# VBT6.net
KiCad netlist of a schematic drawn in Altium Designer
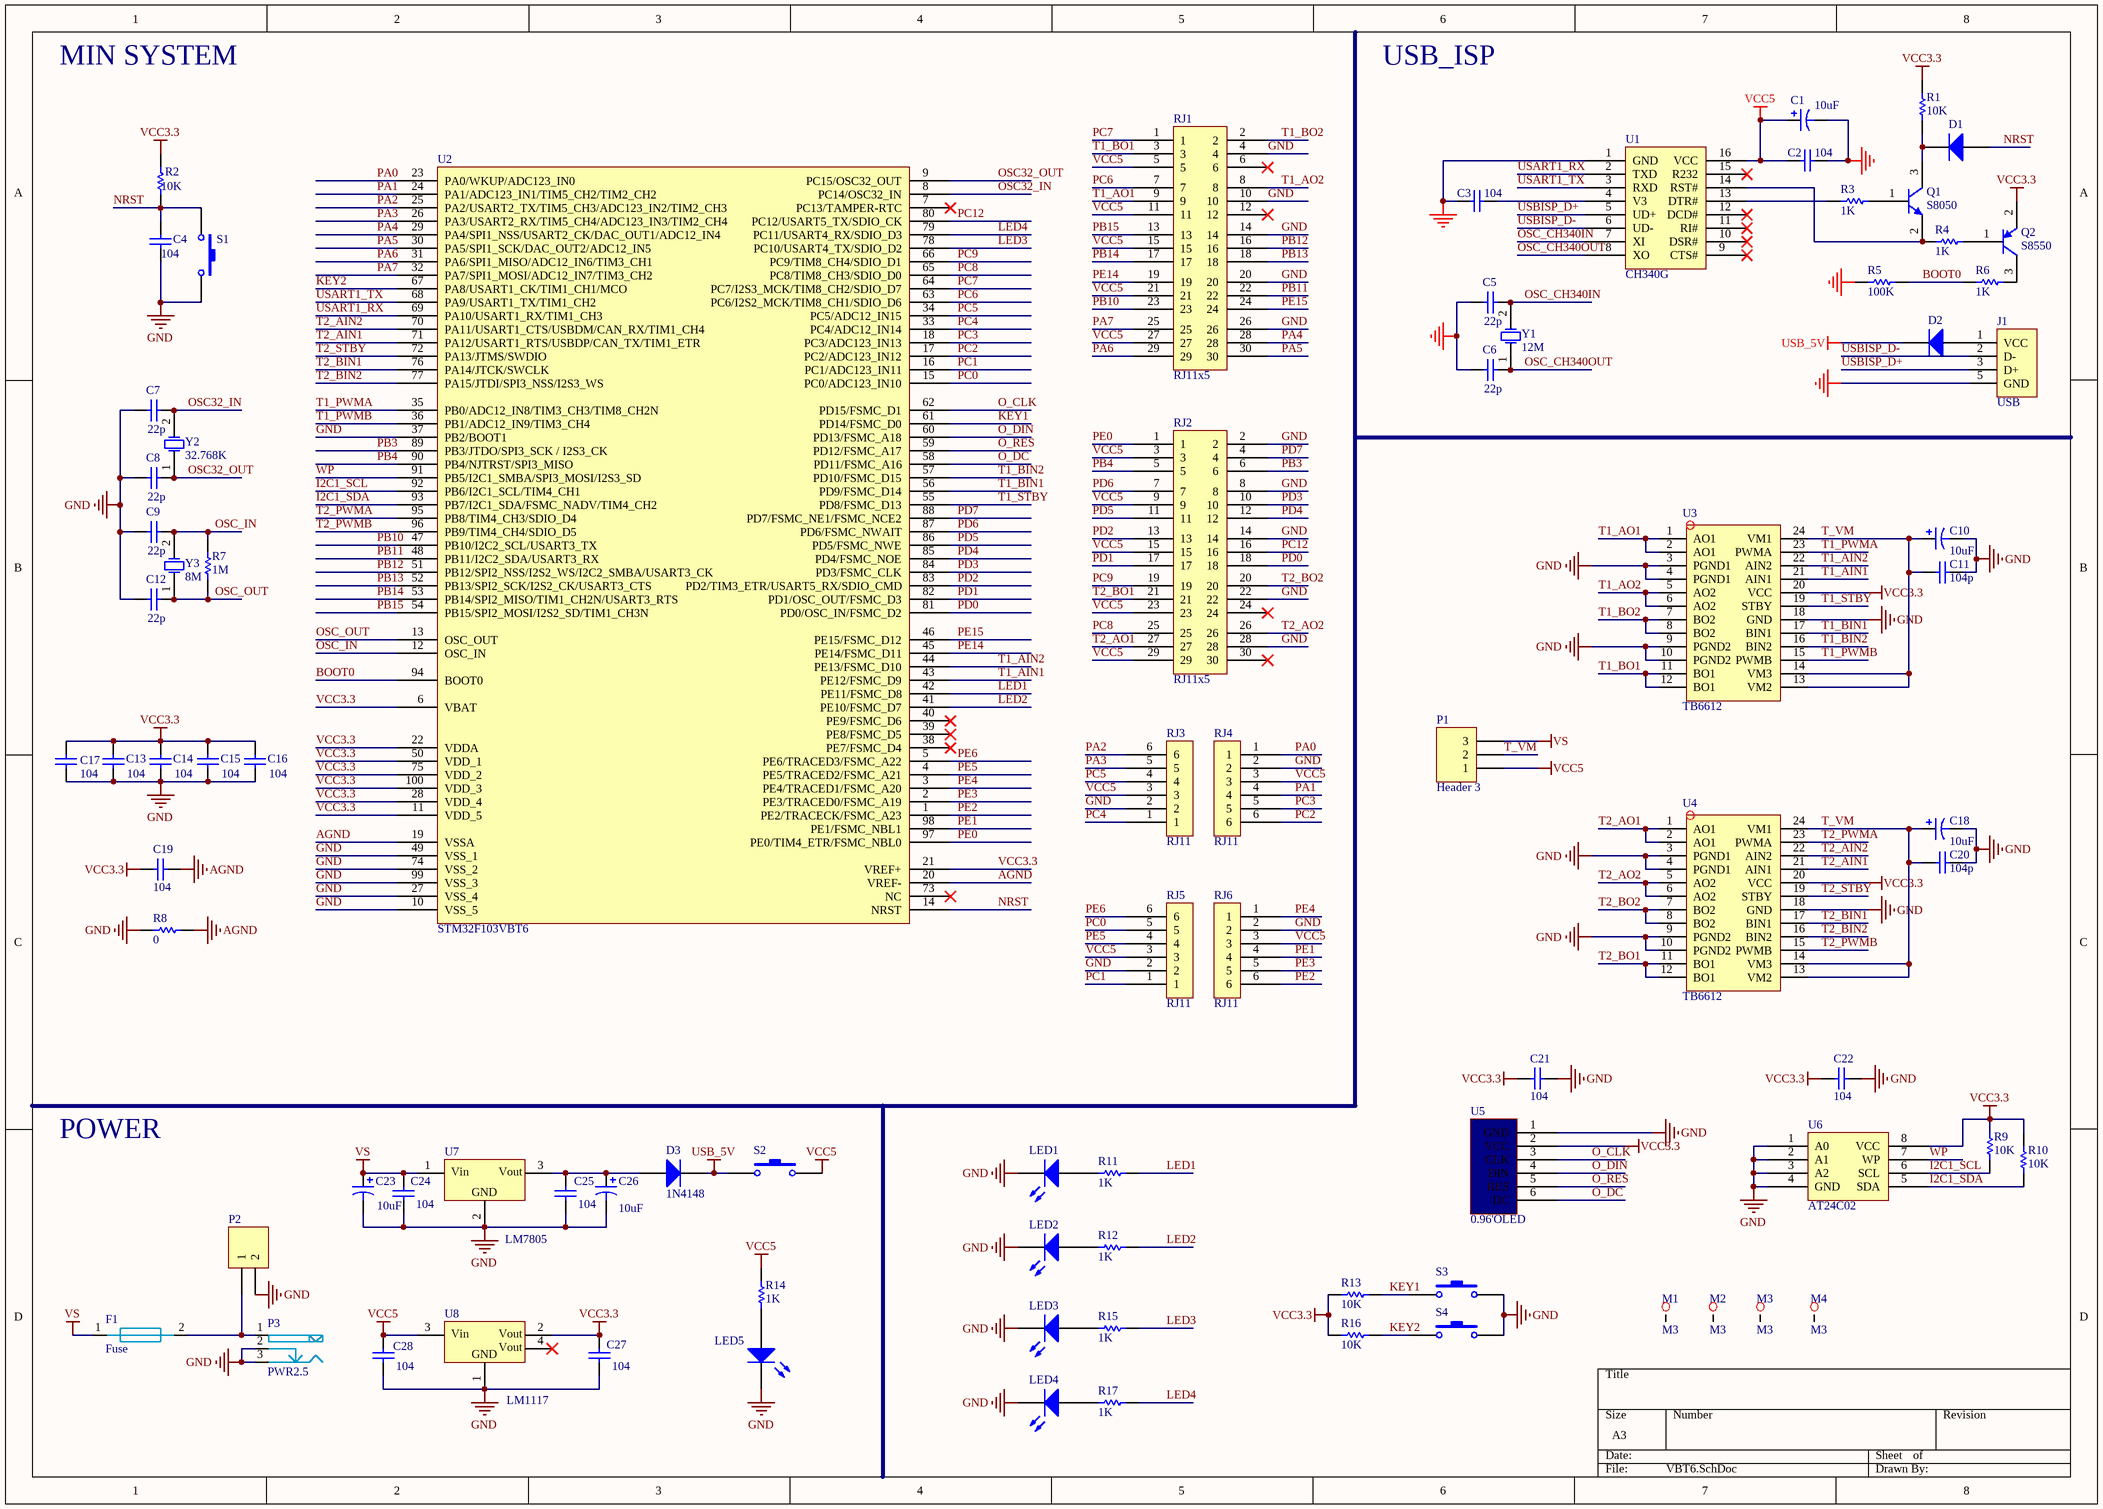
[diagram p0: VBT6.SchDoc]

(export (version "E")
  (design (tool "Eeschema 10.0.6"))
  (components
    (comp (ref "C1")
      (value "10uF")
      (footprint "3528")
      (description "Polarized Capacitor (Surface Mount)")
      (fields (field (name "Comment") "Cap Pol3"))
      (libsource (lib "Miscellaneous Devices") (part "Cap Pol3"))
    )
    (comp (ref "C2")
      (value "104")
      (footprint "0603_C")
      (description "Capacitor")
      (fields (field (name "Comment") "Cap"))
      (libsource (lib "Miscellaneous Devices") (part "Cap"))
    )
    (comp (ref "C3")
      (value "104")
      (footprint "0603_C")
      (description "Capacitor")
      (fields (field (name "Comment") "Cap"))
      (libsource (lib "Miscellaneous Devices") (part "Cap"))
    )
    (comp (ref "C4")
      (value "104")
      (footprint "0603_C")
      (description "Capacitor")
      (fields (field (name "Comment") "Cap"))
      (libsource (lib "Miscellaneous Devices") (part "Cap"))
    )
    (comp (ref "C5")
      (value "22p")
      (footprint "0603_C")
      (description "Capacitor")
      (fields (field (name "Comment") "Cap"))
      (libsource (lib "Miscellaneous Devices") (part "Cap"))
    )
    (comp (ref "C6")
      (value "22p")
      (footprint "0603_C")
      (description "Capacitor")
      (fields (field (name "Comment") "Cap"))
      (libsource (lib "Miscellaneous Devices") (part "Cap"))
    )
    (comp (ref "C7")
      (value "22p")
      (footprint "0603_C")
      (description "Capacitor")
      (fields (field (name "Comment") "Cap"))
      (libsource (lib "Miscellaneous Devices") (part "Cap"))
    )
    (comp (ref "C8")
      (value "22p")
      (footprint "0603_C")
      (description "Capacitor")
      (fields (field (name "Comment") "Cap"))
      (libsource (lib "Miscellaneous Devices") (part "Cap"))
    )
    (comp (ref "C9")
      (value "22p")
      (footprint "0603_C")
      (description "Capacitor")
      (fields (field (name "Comment") "Cap"))
      (libsource (lib "Miscellaneous Devices") (part "Cap"))
    )
    (comp (ref "C10")
      (value "10uF")
      (footprint "电解电容")
      (description "Polarized Capacitor (Surface Mount)")
      (fields (field (name "Comment") "Cap Pol3"))
      (libsource (lib "Miscellaneous Devices") (part "Cap Pol3"))
    )
    (comp (ref "C11")
      (value "104p")
      (footprint "0603_C")
      (description "Capacitor")
      (fields (field (name "Comment") "Cap"))
      (libsource (lib "Miscellaneous Devices") (part "Cap"))
    )
    (comp (ref "C12")
      (value "22p")
      (footprint "0603_C")
      (description "Capacitor")
      (fields (field (name "Comment") "Cap"))
      (libsource (lib "Miscellaneous Devices") (part "Cap"))
    )
    (comp (ref "C13")
      (value "104")
      (footprint "0603_C")
      (description "Capacitor")
      (fields (field (name "Comment") "Cap"))
      (libsource (lib "Miscellaneous Devices") (part "Cap"))
    )
    (comp (ref "C14")
      (value "104")
      (footprint "0603_C")
      (description "Capacitor")
      (fields (field (name "Comment") "Cap"))
      (libsource (lib "Miscellaneous Devices") (part "Cap"))
    )
    (comp (ref "C15")
      (value "104")
      (footprint "0603_C")
      (description "Capacitor")
      (fields (field (name "Comment") "Cap"))
      (libsource (lib "Miscellaneous Devices") (part "Cap"))
    )
    (comp (ref "C16")
      (value "104")
      (footprint "0603_C")
      (description "Capacitor")
      (fields (field (name "Comment") "Cap"))
      (libsource (lib "Miscellaneous Devices") (part "Cap"))
    )
    (comp (ref "C17")
      (value "104")
      (footprint "0603_C")
      (description "Capacitor")
      (fields (field (name "Comment") "Cap"))
      (libsource (lib "Miscellaneous Devices") (part "Cap"))
    )
    (comp (ref "C18")
      (value "10uF")
      (footprint "电解电容")
      (description "Polarized Capacitor (Surface Mount)")
      (fields (field (name "Comment") "Cap Pol3"))
      (libsource (lib "Miscellaneous Devices") (part "Cap Pol3"))
    )
    (comp (ref "C19")
      (value "104")
      (footprint "0603_C")
      (description "Capacitor")
      (fields (field (name "Comment") "Cap"))
      (libsource (lib "Miscellaneous Devices") (part "Cap"))
    )
    (comp (ref "C20")
      (value "104p")
      (footprint "0603_C")
      (description "Capacitor")
      (fields (field (name "Comment") "Cap"))
      (libsource (lib "Miscellaneous Devices") (part "Cap"))
    )
    (comp (ref "C21")
      (value "104")
      (footprint "0603_C")
      (description "Capacitor")
      (fields (field (name "Comment") "Cap"))
      (libsource (lib "Miscellaneous Devices") (part "Cap"))
    )
    (comp (ref "C22")
      (value "104")
      (footprint "0603_C")
      (description "Capacitor")
      (fields (field (name "Comment") "Cap"))
      (libsource (lib "Miscellaneous Devices") (part "Cap"))
    )
    (comp (ref "C23")
      (value "10uF")
      (footprint "3528")
      (description "Polarized Capacitor (Surface Mount)")
      (fields (field (name "Comment") "Cap Pol3"))
      (libsource (lib "Miscellaneous Devices") (part "Cap Pol3"))
    )
    (comp (ref "C24")
      (value "104")
      (footprint "0603_C")
      (description "Capacitor")
      (fields (field (name "Comment") "Cap"))
      (libsource (lib "Miscellaneous Devices") (part "Cap"))
    )
    (comp (ref "C25")
      (value "104")
      (footprint "0603_C")
      (description "Capacitor")
      (fields (field (name "Comment") "Cap"))
      (libsource (lib "Miscellaneous Devices") (part "Cap"))
    )
    (comp (ref "C26")
      (value "10uF")
      (footprint "3528")
      (description "Polarized Capacitor (Surface Mount)")
      (fields (field (name "Comment") "Cap Pol3"))
      (libsource (lib "Miscellaneous Devices") (part "Cap Pol3"))
    )
    (comp (ref "C27")
      (value "104")
      (footprint "0603_C")
      (description "Capacitor")
      (fields (field (name "Comment") "Cap"))
      (libsource (lib "Miscellaneous Devices") (part "Cap"))
    )
    (comp (ref "C28")
      (value "104")
      (footprint "0603_C")
      (description "Capacitor")
      (fields (field (name "Comment") "Cap"))
      (libsource (lib "Miscellaneous Devices") (part "Cap"))
    )
    (comp (ref "D1")
      (value "Diode 1N4001")
      (footprint "SS24")
      (description "1 Amp General Purpose Rectifier")
      (libsource (lib "Miscellaneous Devices") (part "Diode 1N4001"))
    )
    (comp (ref "D2")
      (value "4148")
      (footprint "SS24")
      (description "High Conductance Fast Diode")
      (libsource (lib "Miscellaneous Devices") (part "Diode 1N4148"))
    )
    (comp (ref "D3")
      (value "1N4148")
      (footprint "SS24")
      (description "1 Amp General Purpose Rectifier")
      (libsource (lib "Miscellaneous Devices") (part "Diode 1N4001"))
    )
    (comp (ref "F1") (value "Fuse") (footprint "SMD-1812") (libsource (lib "C8T6开发板") (part "Fuse")))
    (comp (ref "J1")
      (value "USB")
      (footprint "MINIUSB")
      (description "Header, 4-Pin")
      (libsource (lib "Miscellaneous Connectors") (part "Header 4"))
    )
    (comp (ref "LED1")
      (value "LED0")
      (footprint "LED-3mm")
      (description "Typical RED GaAs LED")
      (libsource (lib "Miscellaneous Devices") (part "LED1"))
    )
    (comp (ref "LED2")
      (value "LED0")
      (footprint "LED-3mm")
      (description "Typical RED GaAs LED")
      (libsource (lib "Miscellaneous Devices") (part "LED1"))
    )
    (comp (ref "LED3")
      (value "LED0")
      (footprint "LED-3mm")
      (description "Typical RED GaAs LED")
      (libsource (lib "Miscellaneous Devices") (part "LED1"))
    )
    (comp (ref "LED4")
      (value "LED0")
      (footprint "LED-3mm")
      (description "Typical RED GaAs LED")
      (libsource (lib "Miscellaneous Devices") (part "LED1"))
    )
    (comp (ref "LED5")
      (value "LED0")
      (footprint "LED-3mm")
      (description "Typical RED GaAs LED")
      (libsource (lib "Miscellaneous Devices") (part "LED1"))
    )
    (comp (ref "M1") (value "M3") (footprint "M3*8") (libsource (lib "QQW-1.SCHLIB") (part "M3")))
    (comp (ref "M2") (value "M3") (footprint "M3*8") (libsource (lib "QQW-1.SCHLIB") (part "M3")))
    (comp (ref "M3") (value "M3") (footprint "M3*8") (libsource (lib "QQW-1.SCHLIB") (part "M3")))
    (comp (ref "M4") (value "M3") (footprint "M3*8") (libsource (lib "QQW-1.SCHLIB") (part "M3")))
    (comp (ref "P1")
      (value "Header 3")
      (footprint "HDR1X3")
      (description "Header, 3-Pin")
      (libsource (lib "Miscellaneous Connectors") (part "Header 3"))
    )
    (comp (ref "P2")
      (value "Header 2")
      (footprint "PWRin")
      (description "Header, 2-Pin")
      (libsource (lib "Miscellaneous Connectors") (part "Header 2"))
    )
    (comp (ref "P3") (value "PWR2.5") (footprint "DC_002") (libsource (lib "C8T6开发板") (part "PWR2.5")))
    (comp (ref "Q1")
      (value "S8050")
      (footprint "SOT-23-3L")
      (description "NPN General Purpose Amplifier")
      (libsource (lib "Miscellaneous Devices") (part "2N3904"))
    )
    (comp (ref "Q2")
      (value "S8550")
      (footprint "SOT-23-3L")
      (description "PNP General Purpose Amplifier")
      (libsource (lib "Miscellaneous Devices") (part "2N3906"))
    )
    (comp (ref "R1")
      (value "10K")
      (footprint "0603_R")
      (description "Resistor")
      (fields (field (name "Comment") "Res1"))
      (libsource (lib "Miscellaneous Devices") (part "Res1"))
    )
    (comp (ref "R2")
      (value "10K")
      (footprint "0603_R")
      (description "Resistor")
      (fields (field (name "Comment") "Res1"))
      (libsource (lib "Miscellaneous Devices") (part "Res1"))
    )
    (comp (ref "R3")
      (value "1K")
      (footprint "0603_R")
      (description "Resistor")
      (fields (field (name "Comment") "Res1"))
      (libsource (lib "Miscellaneous Devices") (part "Res1"))
    )
    (comp (ref "R4")
      (value "1K")
      (footprint "0603_R")
      (description "Resistor")
      (fields (field (name "Comment") "Res1"))
      (libsource (lib "Miscellaneous Devices") (part "Res1"))
    )
    (comp (ref "R5")
      (value "100K")
      (footprint "0603_R")
      (description "Resistor")
      (fields (field (name "Comment") "Res1"))
      (libsource (lib "Miscellaneous Devices") (part "Res1"))
    )
    (comp (ref "R6")
      (value "1K")
      (footprint "0603_R")
      (description "Resistor")
      (fields (field (name "Comment") "Res1"))
      (libsource (lib "Miscellaneous Devices") (part "Res1"))
    )
    (comp (ref "R7")
      (value "1M")
      (footprint "0603_R")
      (description "Resistor")
      (fields (field (name "Comment") "Res1"))
      (libsource (lib "Miscellaneous Devices") (part "Res1"))
    )
    (comp (ref "R8")
      (value "0")
      (footprint "0603_R")
      (description "Resistor")
      (fields (field (name "Comment") "Res1"))
      (libsource (lib "Miscellaneous Devices") (part "Res1"))
    )
    (comp (ref "R9")
      (value "10K")
      (footprint "0603_R")
      (description "Resistor")
      (fields (field (name "Comment") "Res1"))
      (libsource (lib "Miscellaneous Devices") (part "Res1"))
    )
    (comp (ref "R10")
      (value "10K")
      (footprint "0603_R")
      (description "Resistor")
      (fields (field (name "Comment") "Res1"))
      (libsource (lib "Miscellaneous Devices") (part "Res1"))
    )
    (comp (ref "R11")
      (value "1K")
      (footprint "0603_R")
      (description "Resistor")
      (fields (field (name "Comment") "Res1"))
      (libsource (lib "Miscellaneous Devices") (part "Res1"))
    )
    (comp (ref "R12")
      (value "1K")
      (footprint "0603_R")
      (description "Resistor")
      (fields (field (name "Comment") "Res1"))
      (libsource (lib "Miscellaneous Devices") (part "Res1"))
    )
    (comp (ref "R13")
      (value "10K")
      (footprint "0603_R")
      (description "Resistor")
      (fields (field (name "Comment") "Res1"))
      (libsource (lib "Miscellaneous Devices") (part "Res1"))
    )
    (comp (ref "R14")
      (value "1K")
      (footprint "0603_R")
      (description "Resistor")
      (fields (field (name "Comment") "Res1"))
      (libsource (lib "Miscellaneous Devices") (part "Res1"))
    )
    (comp (ref "R15")
      (value "1K")
      (footprint "0603_R")
      (description "Resistor")
      (fields (field (name "Comment") "Res1"))
      (libsource (lib "Miscellaneous Devices") (part "Res1"))
    )
    (comp (ref "R16")
      (value "10K")
      (footprint "0603_R")
      (description "Resistor")
      (fields (field (name "Comment") "Res1"))
      (libsource (lib "Miscellaneous Devices") (part "Res1"))
    )
    (comp (ref "R17")
      (value "1K")
      (footprint "0603_R")
      (description "Resistor")
      (fields (field (name "Comment") "Res1"))
      (libsource (lib "Miscellaneous Devices") (part "Res1"))
    )
    (comp (ref "RJ1") (value "RJ11x5") (footprint "RJ11x5") (libsource (lib "VBT6") (part "RJ11x5")))
    (comp (ref "RJ2") (value "RJ11x5") (footprint "RJ11x5") (libsource (lib "VBT6") (part "RJ11x5")))
    (comp (ref "RJ3") (value "RJ11") (footprint "RJ11") (libsource (lib "") (part "RJ11_1")))
    (comp (ref "RJ4") (value "RJ11") (footprint "RJ11") (libsource (lib "VBT6") (part "RJ11")))
    (comp (ref "RJ5") (value "RJ11") (footprint "RJ11") (libsource (lib "") (part "RJ11_1")))
    (comp (ref "RJ6") (value "RJ11") (footprint "RJ11") (libsource (lib "VBT6") (part "RJ11")))
    (comp (ref "S1")
      (value "K1")
      (footprint "KEY_DIP")
      (description "Switch")
      (libsource (lib "Miscellaneous Devices") (part "SW-PB"))
    )
    (comp (ref "S2")
      (value "K1")
      (footprint "SMTS-102C3")
      (description "Switch")
      (libsource (lib "Miscellaneous Devices") (part "SW-PB"))
    )
    (comp (ref "S3")
      (value "K1")
      (footprint "KEY_DIP")
      (description "Switch")
      (libsource (lib "Miscellaneous Devices") (part "SW-PB"))
    )
    (comp (ref "S4")
      (value "K1")
      (footprint "KEY_DIP")
      (description "Switch")
      (libsource (lib "Miscellaneous Devices") (part "SW-PB"))
    )
    (comp (ref "U1") (value "CH340G") (footprint "CH340G") (libsource (lib "少儿智能车") (part "CH340G")))
    (comp (ref "U2")
      (value "STM32F103VBT6")
      (footprint "STM32F103CVBT6")
      (libsource (lib "VBT6") (part "STM32F103VBT6"))
    )
    (comp (ref "U3") (value "TB6612") (footprint "SSOP-24") (libsource (lib "TWSBR") (part "TB6612")))
    (comp (ref "U4") (value "TB6612") (footprint "SSOP-24") (libsource (lib "TWSBR") (part "TB6612")))
    (comp (ref "U5") (value "0.96'OLED") (footprint "OLED") (libsource (lib "STC15") (part "0.96'OLED")))
    (comp (ref "U6") (value "AT24C02") (footprint "SO-8") (libsource (lib "少儿智能车") (part "AT24C02")))
    (comp (ref "U7") (value "LM7805") (footprint "TO-252") (libsource (lib "少儿智能车") (part "LM7805")))
    (comp (ref "U8") (value "LM1117") (footprint "LM117") (libsource (lib "少儿智能车") (part "LM117")))
    (comp (ref "Y1")
      (value "12M")
      (footprint "XTAL12M")
      (description "Crystal Oscillator")
      (libsource (lib "Miscellaneous Devices") (part "XTAL"))
    )
    (comp (ref "Y2")
      (value "32.768K")
      (footprint "XTAL32.768K")
      (description "Crystal Oscillator")
      (libsource (lib "Miscellaneous Devices") (part "XTAL"))
    )
    (comp (ref "Y3")
      (value "8M")
      (footprint "XTAL12M")
      (description "Crystal Oscillator")
      (libsource (lib "Miscellaneous Devices") (part "XTAL"))
    )
  )
  (nets
    (net (code "1") (name "/BOOT0") (class "Default")
      (node (ref "R5") (pin "2") (pinfunction "2_2") (pintype "passive"))
      (node (ref "R6") (pin "2") (pinfunction "2_2") (pintype "passive"))
      (node (ref "U2") (pin "94") (pinfunction "BOOT0_94") (pintype "passive"))
    )
    (net (code "2") (name "/I2C1_SCL") (class "Default")
      (node (ref "R9") (pin "2") (pinfunction "2_2") (pintype "passive"))
      (node (ref "U2") (pin "92") (pinfunction "PB6/I2C1_SCL/TIM4_CH1_92") (pintype "passive"))
      (node (ref "U6") (pin "6") (pinfunction "SCL_6") (pintype "passive"))
    )
    (net (code "3") (name "/I2C1_SDA") (class "Default")
      (node (ref "R10") (pin "2") (pinfunction "2_2") (pintype "passive"))
      (node (ref "U2") (pin "93") (pinfunction "PB7/I2C1_SDA/FSMC_NADV/TIM4_CH2_93") (pintype "passive"))
      (node (ref "U6") (pin "5") (pinfunction "SDA_5") (pintype "passive"))
    )
    (net (code "4") (name "/KEY1") (class "Default")
      (node (ref "R13") (pin "2") (pinfunction "2_2") (pintype "passive"))
      (node (ref "S3") (pin "1") (pinfunction "1_1") (pintype "passive"))
      (node (ref "U2") (pin "61") (pinfunction "PD14/FSMC_D0_61") (pintype "passive"))
    )
    (net (code "5") (name "/KEY2") (class "Default")
      (node (ref "R16") (pin "2") (pinfunction "2_2") (pintype "passive"))
      (node (ref "S4") (pin "1") (pinfunction "1_1") (pintype "passive"))
      (node (ref "U2") (pin "67") (pinfunction "PA8/USART1_CK/TIM1_CH1/MCO_67") (pintype "passive"))
    )
    (net (code "6") (name "/LED1") (class "Default")
      (node (ref "R11") (pin "2") (pinfunction "2_2") (pintype "passive"))
      (node (ref "U2") (pin "42") (pinfunction "PE11/FSMC_D8_42") (pintype "passive"))
    )
    (net (code "7") (name "/LED2") (class "Default")
      (node (ref "R12") (pin "2") (pinfunction "2_2") (pintype "passive"))
      (node (ref "U2") (pin "41") (pinfunction "PE10/FSMC_D7_41") (pintype "passive"))
    )
    (net (code "8") (name "/LED3") (class "Default")
      (node (ref "R15") (pin "2") (pinfunction "2_2") (pintype "passive"))
      (node (ref "U2") (pin "78") (pinfunction "PC10/USART4_TX/SDIO_D2_78") (pintype "passive"))
    )
    (net (code "9") (name "/LED4") (class "Default")
      (node (ref "R17") (pin "2") (pinfunction "2_2") (pintype "passive"))
      (node (ref "U2") (pin "79") (pinfunction "PC11/USART4_RX/SDIO_D3_79") (pintype "passive"))
    )
    (net (code "10") (name "/NRST") (class "Default")
      (node (ref "C4") (pin "2") (pinfunction "2_2") (pintype "passive"))
      (node (ref "D1") (pin "1") (pinfunction "A_1") (pintype "passive"))
      (node (ref "R2") (pin "1") (pinfunction "1_1") (pintype "passive"))
      (node (ref "S1") (pin "1") (pinfunction "1_1") (pintype "passive"))
      (node (ref "U2") (pin "14") (pinfunction "NRST_14") (pintype "passive"))
    )
    (net (code "11") (name "/OSC32_IN") (class "Default")
      (node (ref "C7") (pin "2") (pinfunction "2_2") (pintype "passive"))
      (node (ref "U2") (pin "8") (pinfunction "PC14/OSC32_IN_8") (pintype "passive"))
      (node (ref "Y2") (pin "2") (pinfunction "OSC2_2") (pintype "passive"))
    )
    (net (code "12") (name "/OSC32_OUT") (class "Default")
      (node (ref "C8") (pin "1") (pinfunction "1_1") (pintype "passive"))
      (node (ref "U2") (pin "9") (pinfunction "PC15/OSC32_OUT_9") (pintype "passive"))
      (node (ref "Y2") (pin "1") (pinfunction "OSC1_1") (pintype "passive"))
    )
    (net (code "13") (name "/OSC_CH340IN") (class "Default")
      (node (ref "C5") (pin "1") (pinfunction "1_1") (pintype "passive"))
      (node (ref "U1") (pin "7") (pinfunction "XI_7") (pintype "passive"))
      (node (ref "Y1") (pin "2") (pinfunction "OSC2_2") (pintype "passive"))
    )
    (net (code "14") (name "/OSC_CH340OUT") (class "Default")
      (node (ref "C6") (pin "1") (pinfunction "1_1") (pintype "passive"))
      (node (ref "U1") (pin "8") (pinfunction "XO_8") (pintype "passive"))
      (node (ref "Y1") (pin "1") (pinfunction "OSC1_1") (pintype "passive"))
    )
    (net (code "15") (name "/OSC_IN") (class "Default")
      (node (ref "C9") (pin "1") (pinfunction "1_1") (pintype "passive"))
      (node (ref "R7") (pin "1") (pinfunction "1_1") (pintype "passive"))
      (node (ref "U2") (pin "12") (pinfunction "OSC_IN_12") (pintype "passive"))
      (node (ref "Y3") (pin "2") (pinfunction "OSC2_2") (pintype "passive"))
    )
    (net (code "16") (name "/OSC_OUT") (class "Default")
      (node (ref "C12") (pin "1") (pinfunction "1_1") (pintype "passive"))
      (node (ref "R7") (pin "2") (pinfunction "2_2") (pintype "passive"))
      (node (ref "U2") (pin "13") (pinfunction "OSC_OUT_13") (pintype "passive"))
      (node (ref "Y3") (pin "1") (pinfunction "OSC1_1") (pintype "passive"))
    )
    (net (code "17") (name "/O_CLK") (class "Default")
      (node (ref "U2") (pin "62") (pinfunction "PD15/FSMC_D1_62") (pintype "passive"))
      (node (ref "U5") (pin "3") (pinfunction "CLK_3") (pintype "passive"))
    )
    (net (code "18") (name "/O_DC") (class "Default")
      (node (ref "U2") (pin "58") (pinfunction "PD11/FSMC_A16_58") (pintype "passive"))
      (node (ref "U5") (pin "6") (pinfunction "DC_6") (pintype "passive"))
    )
    (net (code "19") (name "/O_DIN") (class "Default")
      (node (ref "U2") (pin "60") (pinfunction "PD13/FSMC_A18_60") (pintype "passive"))
      (node (ref "U5") (pin "4") (pinfunction "DIN_4") (pintype "passive"))
    )
    (net (code "20") (name "/O_RES") (class "Default")
      (node (ref "U2") (pin "59") (pinfunction "PD12/FSMC_A17_59") (pintype "passive"))
      (node (ref "U5") (pin "5") (pinfunction "RES_5") (pintype "passive"))
    )
    (net (code "21") (name "/PA0") (class "Default")
      (node (ref "RJ4") (pin "1") (pinfunction "1_1") (pintype "passive"))
      (node (ref "U2") (pin "23") (pinfunction "PA0/WKUP/ADC123_IN0_23") (pintype "passive"))
    )
    (net (code "22") (name "/PA1") (class "Default")
      (node (ref "RJ4") (pin "4") (pinfunction "4_4") (pintype "passive"))
      (node (ref "U2") (pin "24") (pinfunction "PA1/ADC123_IN1/TIM5_CH2/TIM2_CH2_24") (pintype "passive"))
    )
    (net (code "23") (name "/PA2") (class "Default")
      (node (ref "RJ3") (pin "6") (pinfunction "6_6") (pintype "passive"))
      (node (ref "U2") (pin "25") (pinfunction "PA2/USART2_TX/TIM5_CH3/ADC123_IN2/TIM2_CH3_25") (pintype "passive"))
    )
    (net (code "24") (name "/PA3") (class "Default")
      (node (ref "RJ3") (pin "5") (pinfunction "5_5") (pintype "passive"))
      (node (ref "U2") (pin "26") (pinfunction "PA3/USART2_RX/TIM5_CH4/ADC123_IN3/TIM2_CH4_26") (pintype "passive"))
    )
    (net (code "25") (name "/PA4") (class "Default")
      (node (ref "RJ1") (pin "28") (pinfunction "28_28") (pintype "passive"))
      (node (ref "U2") (pin "29") (pinfunction "PA4/SPI1_NSS/USART2_CK/DAC_OUT1/ADC12_IN4_29") (pintype "passive"))
    )
    (net (code "26") (name "/PA5") (class "Default")
      (node (ref "RJ1") (pin "30") (pinfunction "30_30") (pintype "passive"))
      (node (ref "U2") (pin "30") (pinfunction "PA5/SPI1_SCK/DAC_OUT2/ADC12_IN5_30") (pintype "passive"))
    )
    (net (code "27") (name "/PA6") (class "Default")
      (node (ref "RJ1") (pin "29") (pinfunction "29_29") (pintype "passive"))
      (node (ref "U2") (pin "31") (pinfunction "PA6/SPI1_MISO/ADC12_IN6/TIM3_CH1_31") (pintype "passive"))
    )
    (net (code "28") (name "/PA7") (class "Default")
      (node (ref "RJ1") (pin "25") (pinfunction "25_25") (pintype "passive"))
      (node (ref "U2") (pin "32") (pinfunction "PA7/SPI1_MOSI/ADC12_IN7/TIM3_CH2_32") (pintype "passive"))
    )
    (net (code "29") (name "/PB3") (class "Default")
      (node (ref "RJ2") (pin "6") (pinfunction "6_6") (pintype "passive"))
      (node (ref "U2") (pin "89") (pinfunction "PB3/JTDO/SPI3_SCK_/_I2S3_CK_89") (pintype "passive"))
    )
    (net (code "30") (name "/PB4") (class "Default")
      (node (ref "RJ2") (pin "5") (pinfunction "5_5") (pintype "passive"))
      (node (ref "U2") (pin "90") (pinfunction "PB4/NJTRST/SPI3_MISO_90") (pintype "passive"))
    )
    (net (code "31") (name "/PB10") (class "Default")
      (node (ref "RJ1") (pin "23") (pinfunction "23_23") (pintype "passive"))
      (node (ref "U2") (pin "47") (pinfunction "PB10/I2C2_SCL/USART3_TX_47") (pintype "passive"))
    )
    (net (code "32") (name "/PB11") (class "Default")
      (node (ref "RJ1") (pin "22") (pinfunction "22_22") (pintype "passive"))
      (node (ref "U2") (pin "48") (pinfunction "PB11/I2C2_SDA/USART3_RX_48") (pintype "passive"))
    )
    (net (code "33") (name "/PB12") (class "Default")
      (node (ref "RJ1") (pin "16") (pinfunction "16_16") (pintype "passive"))
      (node (ref "U2") (pin "51") (pinfunction "PB12/SPI2_NSS/I2S2_WS/I2C2_SMBA/USART3_CK_51") (pintype "passive"))
    )
    (net (code "34") (name "/PB13") (class "Default")
      (node (ref "RJ1") (pin "18") (pinfunction "18_18") (pintype "passive"))
      (node (ref "U2") (pin "52") (pinfunction "PB13/SPI2_SCK/I2S2_CK/USART3_CTS_52") (pintype "passive"))
    )
    (net (code "35") (name "/PB14") (class "Default")
      (node (ref "RJ1") (pin "17") (pinfunction "17_17") (pintype "passive"))
      (node (ref "U2") (pin "53") (pinfunction "PB14/SPI2_MISO/TIM1_CH2N/USART3_RTS_53") (pintype "passive"))
    )
    (net (code "36") (name "/PB15") (class "Default")
      (node (ref "RJ1") (pin "13") (pinfunction "13_13") (pintype "passive"))
      (node (ref "U2") (pin "54") (pinfunction "PB15/SPI2_MOSI/I2S2_SD/TIM1_CH3N_54") (pintype "passive"))
    )
    (net (code "37") (name "/PC0") (class "Default")
      (node (ref "RJ5") (pin "5") (pinfunction "5_5") (pintype "passive"))
      (node (ref "U2") (pin "15") (pinfunction "PC0/ADC123_IN10_15") (pintype "passive"))
    )
    (net (code "38") (name "/PC1") (class "Default")
      (node (ref "RJ5") (pin "1") (pinfunction "1_1") (pintype "passive"))
      (node (ref "U2") (pin "16") (pinfunction "PC1/ADC123_IN11_16") (pintype "passive"))
    )
    (net (code "39") (name "/PC2") (class "Default")
      (node (ref "RJ4") (pin "6") (pinfunction "6_6") (pintype "passive"))
      (node (ref "U2") (pin "17") (pinfunction "PC2/ADC123_IN12_17") (pintype "passive"))
    )
    (net (code "40") (name "/PC3") (class "Default")
      (node (ref "RJ4") (pin "5") (pinfunction "5_5") (pintype "passive"))
      (node (ref "U2") (pin "18") (pinfunction "PC3/ADC123_IN13_18") (pintype "passive"))
    )
    (net (code "41") (name "/PC4") (class "Default")
      (node (ref "RJ3") (pin "1") (pinfunction "1_1") (pintype "passive"))
      (node (ref "U2") (pin "33") (pinfunction "PC4/ADC12_IN14_33") (pintype "passive"))
    )
    (net (code "42") (name "/PC5") (class "Default")
      (node (ref "RJ3") (pin "4") (pinfunction "4_4") (pintype "passive"))
      (node (ref "U2") (pin "34") (pinfunction "PC5/ADC12_IN15_34") (pintype "passive"))
    )
    (net (code "43") (name "/PC6") (class "Default")
      (node (ref "RJ1") (pin "7") (pinfunction "7_7") (pintype "passive"))
      (node (ref "U2") (pin "63") (pinfunction "PC6/I2S2_MCK/TIM8_CH1/SDIO_D6_63") (pintype "passive"))
    )
    (net (code "44") (name "/PC7") (class "Default")
      (node (ref "RJ1") (pin "1") (pinfunction "1_1") (pintype "passive"))
      (node (ref "U2") (pin "64") (pinfunction "PC7/I2S3_MCK/TIM8_CH2/SDIO_D7_64") (pintype "passive"))
    )
    (net (code "45") (name "/PC8") (class "Default")
      (node (ref "RJ2") (pin "25") (pinfunction "25_25") (pintype "passive"))
      (node (ref "U2") (pin "65") (pinfunction "PC8/TIM8_CH3/SDIO_D0_65") (pintype "passive"))
    )
    (net (code "46") (name "/PC9") (class "Default")
      (node (ref "RJ2") (pin "19") (pinfunction "19_19") (pintype "passive"))
      (node (ref "U2") (pin "66") (pinfunction "PC9/TIM8_CH4/SDIO_D1_66") (pintype "passive"))
    )
    (net (code "47") (name "/PC12") (class "Default")
      (node (ref "RJ2") (pin "16") (pinfunction "16_16") (pintype "passive"))
      (node (ref "U2") (pin "80") (pinfunction "PC12/USART5_TX/SDIO_CK_80") (pintype "passive"))
    )
    (net (code "48") (name "/PD0") (class "Default")
      (node (ref "RJ2") (pin "18") (pinfunction "18_18") (pintype "passive"))
      (node (ref "U2") (pin "81") (pinfunction "PD0/OSC_IN/FSMC_D2_81") (pintype "passive"))
    )
    (net (code "49") (name "/PD1") (class "Default")
      (node (ref "RJ2") (pin "17") (pinfunction "17_17") (pintype "passive"))
      (node (ref "U2") (pin "82") (pinfunction "PD1/OSC_OUT/FSMC_D3_82") (pintype "passive"))
    )
    (net (code "50") (name "/PD2") (class "Default")
      (node (ref "RJ2") (pin "13") (pinfunction "13_13") (pintype "passive"))
      (node (ref "U2") (pin "83") (pinfunction "PD2/TIM3_ETR/USART5_RX/SDIO_CMD_83") (pintype "passive"))
    )
    (net (code "51") (name "/PD3") (class "Default")
      (node (ref "RJ2") (pin "10") (pinfunction "10_10") (pintype "passive"))
      (node (ref "U2") (pin "84") (pinfunction "PD3/FSMC_CLK_84") (pintype "passive"))
    )
    (net (code "52") (name "/PD4") (class "Default")
      (node (ref "RJ2") (pin "12") (pinfunction "12_12") (pintype "passive"))
      (node (ref "U2") (pin "85") (pinfunction "PD4/FSMC_NOE_85") (pintype "passive"))
    )
    (net (code "53") (name "/PD5") (class "Default")
      (node (ref "RJ2") (pin "11") (pinfunction "11_11") (pintype "passive"))
      (node (ref "U2") (pin "86") (pinfunction "PD5/FSMC_NWE_86") (pintype "passive"))
    )
    (net (code "54") (name "/PD6") (class "Default")
      (node (ref "RJ2") (pin "7") (pinfunction "7_7") (pintype "passive"))
      (node (ref "U2") (pin "87") (pinfunction "PD6/FSMC_NWAIT_87") (pintype "passive"))
    )
    (net (code "55") (name "/PD7") (class "Default")
      (node (ref "RJ2") (pin "4") (pinfunction "4_4") (pintype "passive"))
      (node (ref "U2") (pin "88") (pinfunction "PD7/FSMC_NE1/FSMC_NCE2_88") (pintype "passive"))
    )
    (net (code "56") (name "/PE0") (class "Default")
      (node (ref "RJ2") (pin "1") (pinfunction "1_1") (pintype "passive"))
      (node (ref "U2") (pin "97") (pinfunction "PE0/TIM4_ETR/FSMC_NBL0_97") (pintype "passive"))
    )
    (net (code "57") (name "/PE1") (class "Default")
      (node (ref "RJ6") (pin "4") (pinfunction "4_4") (pintype "passive"))
      (node (ref "U2") (pin "98") (pinfunction "PE1/FSMC_NBL1_98") (pintype "passive"))
    )
    (net (code "58") (name "/PE2") (class "Default")
      (node (ref "RJ6") (pin "6") (pinfunction "6_6") (pintype "passive"))
      (node (ref "U2") (pin "1") (pinfunction "PE2/TRACECK/FSMC_A23_1") (pintype "passive"))
    )
    (net (code "59") (name "/PE3") (class "Default")
      (node (ref "RJ6") (pin "5") (pinfunction "5_5") (pintype "passive"))
      (node (ref "U2") (pin "2") (pinfunction "PE3/TRACED0/FSMC_A19_2") (pintype "passive"))
    )
    (net (code "60") (name "/PE4") (class "Default")
      (node (ref "RJ6") (pin "1") (pinfunction "1_1") (pintype "passive"))
      (node (ref "U2") (pin "3") (pinfunction "PE4/TRACED1/FSMC_A20_3") (pintype "passive"))
    )
    (net (code "61") (name "/PE5") (class "Default")
      (node (ref "RJ5") (pin "4") (pinfunction "4_4") (pintype "passive"))
      (node (ref "U2") (pin "4") (pinfunction "PE5/TRACED2/FSMC_A21_4") (pintype "passive"))
    )
    (net (code "62") (name "/PE6") (class "Default")
      (node (ref "RJ5") (pin "6") (pinfunction "6_6") (pintype "passive"))
      (node (ref "U2") (pin "5") (pinfunction "PE6/TRACED3/FSMC_A22_5") (pintype "passive"))
    )
    (net (code "63") (name "/PE14") (class "Default")
      (node (ref "RJ1") (pin "19") (pinfunction "19_19") (pintype "passive"))
      (node (ref "U2") (pin "45") (pinfunction "PE14/FSMC_D11_45") (pintype "passive"))
    )
    (net (code "64") (name "/PE15") (class "Default")
      (node (ref "RJ1") (pin "24") (pinfunction "24_24") (pintype "passive"))
      (node (ref "U2") (pin "46") (pinfunction "PE15/FSMC_D12_46") (pintype "passive"))
    )
    (net (code "65") (name "/T1_AIN1") (class "Default")
      (node (ref "U2") (pin "43") (pinfunction "PE12/FSMC_D9_43") (pintype "passive"))
      (node (ref "U3") (pin "21") (pinfunction "AIN1_21") (pintype "passive"))
    )
    (net (code "66") (name "/T1_AIN2") (class "Default")
      (node (ref "U2") (pin "44") (pinfunction "PE13/FSMC_D10_44") (pintype "passive"))
      (node (ref "U3") (pin "22") (pinfunction "AIN2_22") (pintype "passive"))
    )
    (net (code "67") (name "/T1_AO1") (class "Default")
      (node (ref "RJ1") (pin "9") (pinfunction "9_9") (pintype "passive"))
      (node (ref "U3") (pin "1") (pinfunction "AO1_1") (pintype "passive"))
      (node (ref "U3") (pin "2") (pinfunction "AO1_2") (pintype "passive"))
    )
    (net (code "68") (name "/T1_AO2") (class "Default")
      (node (ref "RJ1") (pin "8") (pinfunction "8_8") (pintype "passive"))
      (node (ref "U3") (pin "5") (pinfunction "AO2_5") (pintype "passive"))
      (node (ref "U3") (pin "6") (pinfunction "AO2_6") (pintype "passive"))
    )
    (net (code "69") (name "/T1_BIN1") (class "Default")
      (node (ref "U2") (pin "56") (pinfunction "PD9/FSMC_D14_56") (pintype "passive"))
      (node (ref "U3") (pin "17") (pinfunction "BIN1_17") (pintype "passive"))
    )
    (net (code "70") (name "/T1_BIN2") (class "Default")
      (node (ref "U2") (pin "57") (pinfunction "PD10/FSMC_D15_57") (pintype "passive"))
      (node (ref "U3") (pin "16") (pinfunction "BIN2_16") (pintype "passive"))
    )
    (net (code "71") (name "/T1_BO1") (class "Default")
      (node (ref "RJ1") (pin "3") (pinfunction "3_3") (pintype "passive"))
      (node (ref "U3") (pin "11") (pinfunction "BO1_11") (pintype "passive"))
      (node (ref "U3") (pin "12") (pinfunction "BO1_12") (pintype "passive"))
    )
    (net (code "72") (name "/T1_BO2") (class "Default")
      (node (ref "RJ1") (pin "2") (pinfunction "2_2") (pintype "passive"))
      (node (ref "U3") (pin "7") (pinfunction "BO2_7") (pintype "passive"))
      (node (ref "U3") (pin "8") (pinfunction "BO2_8") (pintype "passive"))
    )
    (net (code "73") (name "/T1_PWMA") (class "Default")
      (node (ref "U2") (pin "35") (pinfunction "PB0/ADC12_IN8/TIM3_CH3/TIM8_CH2N_35") (pintype "passive"))
      (node (ref "U3") (pin "23") (pinfunction "PWMA_23") (pintype "passive"))
    )
    (net (code "74") (name "/T1_PWMB") (class "Default")
      (node (ref "U2") (pin "36") (pinfunction "PB1/ADC12_IN9/TIM3_CH4_36") (pintype "passive"))
      (node (ref "U3") (pin "15") (pinfunction "PWMB_15") (pintype "passive"))
    )
    (net (code "75") (name "/T1_STBY") (class "Default")
      (node (ref "U2") (pin "55") (pinfunction "PD8/FSMC_D13_55") (pintype "passive"))
      (node (ref "U3") (pin "19") (pinfunction "STBY_19") (pintype "passive"))
    )
    (net (code "76") (name "/T2_AIN1") (class "Default")
      (node (ref "U2") (pin "71") (pinfunction "PA12/USART1_RTS/USBDP/CAN_TX/TIM1_ETR_71") (pintype "passive"))
      (node (ref "U4") (pin "21") (pinfunction "AIN1_21") (pintype "passive"))
    )
    (net (code "77") (name "/T2_AIN2") (class "Default")
      (node (ref "U2") (pin "70") (pinfunction "PA11/USART1_CTS/USBDM/CAN_RX/TIM1_CH4_70") (pintype "passive"))
      (node (ref "U4") (pin "22") (pinfunction "AIN2_22") (pintype "passive"))
    )
    (net (code "78") (name "/T2_AO1") (class "Default")
      (node (ref "RJ2") (pin "27") (pinfunction "27_27") (pintype "passive"))
      (node (ref "U4") (pin "1") (pinfunction "AO1_1") (pintype "passive"))
      (node (ref "U4") (pin "2") (pinfunction "AO1_2") (pintype "passive"))
    )
    (net (code "79") (name "/T2_AO2") (class "Default")
      (node (ref "RJ2") (pin "26") (pinfunction "26_26") (pintype "passive"))
      (node (ref "U4") (pin "5") (pinfunction "AO2_5") (pintype "passive"))
      (node (ref "U4") (pin "6") (pinfunction "AO2_6") (pintype "passive"))
    )
    (net (code "80") (name "/T2_BIN1") (class "Default")
      (node (ref "U2") (pin "76") (pinfunction "PA14/JTCK/SWCLK_76") (pintype "passive"))
      (node (ref "U4") (pin "17") (pinfunction "BIN1_17") (pintype "passive"))
    )
    (net (code "81") (name "/T2_BIN2") (class "Default")
      (node (ref "U2") (pin "77") (pinfunction "PA15/JTDI/SPI3_NSS/I2S3_WS_77") (pintype "passive"))
      (node (ref "U4") (pin "16") (pinfunction "BIN2_16") (pintype "passive"))
    )
    (net (code "82") (name "/T2_BO1") (class "Default")
      (node (ref "RJ2") (pin "21") (pinfunction "21_21") (pintype "passive"))
      (node (ref "U4") (pin "11") (pinfunction "BO1_11") (pintype "passive"))
      (node (ref "U4") (pin "12") (pinfunction "BO1_12") (pintype "passive"))
    )
    (net (code "83") (name "/T2_BO2") (class "Default")
      (node (ref "RJ2") (pin "20") (pinfunction "20_20") (pintype "passive"))
      (node (ref "U4") (pin "7") (pinfunction "BO2_7") (pintype "passive"))
      (node (ref "U4") (pin "8") (pinfunction "BO2_8") (pintype "passive"))
    )
    (net (code "84") (name "/T2_PWMA") (class "Default")
      (node (ref "U2") (pin "95") (pinfunction "PB8/TIM4_CH3/SDIO_D4_95") (pintype "passive"))
      (node (ref "U4") (pin "23") (pinfunction "PWMA_23") (pintype "passive"))
    )
    (net (code "85") (name "/T2_PWMB") (class "Default")
      (node (ref "U2") (pin "96") (pinfunction "PB9/TIM4_CH4/SDIO_D5_96") (pintype "passive"))
      (node (ref "U4") (pin "15") (pinfunction "PWMB_15") (pintype "passive"))
    )
    (net (code "86") (name "/T2_STBY") (class "Default")
      (node (ref "U2") (pin "72") (pinfunction "PA13/JTMS/SWDIO_72") (pintype "passive"))
      (node (ref "U4") (pin "19") (pinfunction "STBY_19") (pintype "passive"))
    )
    (net (code "87") (name "/T_VM") (class "Default")
      (node (ref "C10") (pin "1") (pinfunction "1_1") (pintype "passive"))
      (node (ref "C11") (pin "2") (pinfunction "2_2") (pintype "passive"))
      (node (ref "C18") (pin "1") (pinfunction "1_1") (pintype "passive"))
      (node (ref "C20") (pin "2") (pinfunction "2_2") (pintype "passive"))
      (node (ref "P1") (pin "2") (pinfunction "2_2") (pintype "passive"))
      (node (ref "U3") (pin "13") (pinfunction "VM2_13") (pintype "passive"))
      (node (ref "U3") (pin "14") (pinfunction "VM3_14") (pintype "passive"))
      (node (ref "U3") (pin "24") (pinfunction "VM1_24") (pintype "passive"))
      (node (ref "U4") (pin "13") (pinfunction "VM2_13") (pintype "passive"))
      (node (ref "U4") (pin "14") (pinfunction "VM3_14") (pintype "passive"))
      (node (ref "U4") (pin "24") (pinfunction "VM1_24") (pintype "passive"))
    )
    (net (code "88") (name "/USART1_RX") (class "Default")
      (node (ref "U1") (pin "2") (pinfunction "TXD_2") (pintype "passive"))
      (node (ref "U2") (pin "69") (pinfunction "PA10/USART1_RX/TIM1_CH3_69") (pintype "passive"))
    )
    (net (code "89") (name "/USART1_TX") (class "Default")
      (node (ref "U1") (pin "3") (pinfunction "RXD_3") (pintype "passive"))
      (node (ref "U2") (pin "68") (pinfunction "PA9/USART1_TX/TIM1_CH2_68") (pintype "passive"))
    )
    (net (code "90") (name "/USBISP_D+") (class "Default")
      (node (ref "J1") (pin "3") (pinfunction "D+_3") (pintype "passive"))
      (node (ref "U1") (pin "5") (pinfunction "UD+_5") (pintype "passive"))
    )
    (net (code "91") (name "/USBISP_D-") (class "Default")
      (node (ref "J1") (pin "2") (pinfunction "D-_2") (pintype "passive"))
      (node (ref "U1") (pin "6") (pinfunction "UD-_6") (pintype "passive"))
    )
    (net (code "92") (name "/WP") (class "Default")
      (node (ref "U2") (pin "91") (pinfunction "PB5/I2C1_SMBA/SPI3_MOSI/I2S3_SD_91") (pintype "passive"))
      (node (ref "U6") (pin "7") (pinfunction "WP_7") (pintype "passive"))
    )
    (net (code "93") (name "AGND") (class "Default")
      (node (ref "C19") (pin "1") (pinfunction "1_1") (pintype "passive"))
      (node (ref "R8") (pin "2") (pinfunction "2_2") (pintype "passive"))
      (node (ref "U2") (pin "19") (pinfunction "VSSA_19") (pintype "passive"))
      (node (ref "U2") (pin "20") (pinfunction "VREF-_20") (pintype "passive"))
    )
    (net (code "94") (name "GND") (class "Default")
      (node (ref "C1") (pin "2") (pinfunction "2_2") (pintype "passive"))
      (node (ref "C10") (pin "2") (pinfunction "2_2") (pintype "passive"))
      (node (ref "C11") (pin "1") (pinfunction "1_1") (pintype "passive"))
      (node (ref "C12") (pin "2") (pinfunction "2_2") (pintype "passive"))
      (node (ref "C13") (pin "1") (pinfunction "1_1") (pintype "passive"))
      (node (ref "C14") (pin "1") (pinfunction "1_1") (pintype "passive"))
      (node (ref "C15") (pin "1") (pinfunction "1_1") (pintype "passive"))
      (node (ref "C16") (pin "1") (pinfunction "1_1") (pintype "passive"))
      (node (ref "C17") (pin "1") (pinfunction "1_1") (pintype "passive"))
      (node (ref "C18") (pin "2") (pinfunction "2_2") (pintype "passive"))
      (node (ref "C2") (pin "2") (pinfunction "2_2") (pintype "passive"))
      (node (ref "C20") (pin "1") (pinfunction "1_1") (pintype "passive"))
      (node (ref "C21") (pin "1") (pinfunction "1_1") (pintype "passive"))
      (node (ref "C22") (pin "1") (pinfunction "1_1") (pintype "passive"))
      (node (ref "C23") (pin "2") (pinfunction "2_2") (pintype "passive"))
      (node (ref "C24") (pin "1") (pinfunction "1_1") (pintype "passive"))
      (node (ref "C25") (pin "1") (pinfunction "1_1") (pintype "passive"))
      (node (ref "C26") (pin "2") (pinfunction "2_2") (pintype "passive"))
      (node (ref "C27") (pin "1") (pinfunction "1_1") (pintype "passive"))
      (node (ref "C28") (pin "1") (pinfunction "1_1") (pintype "passive"))
      (node (ref "C3") (pin "1") (pinfunction "1_1") (pintype "passive"))
      (node (ref "C4") (pin "1") (pinfunction "1_1") (pintype "passive"))
      (node (ref "C5") (pin "2") (pinfunction "2_2") (pintype "passive"))
      (node (ref "C6") (pin "2") (pinfunction "2_2") (pintype "passive"))
      (node (ref "C7") (pin "1") (pinfunction "1_1") (pintype "passive"))
      (node (ref "C8") (pin "2") (pinfunction "2_2") (pintype "passive"))
      (node (ref "C9") (pin "2") (pinfunction "2_2") (pintype "passive"))
      (node (ref "J1") (pin "5") (pinfunction "GND_5") (pintype "passive"))
      (node (ref "LED1") (pin "2") (pinfunction "K_2") (pintype "passive"))
      (node (ref "LED2") (pin "2") (pinfunction "K_2") (pintype "passive"))
      (node (ref "LED3") (pin "2") (pinfunction "K_2") (pintype "passive"))
      (node (ref "LED4") (pin "2") (pinfunction "K_2") (pintype "passive"))
      (node (ref "LED5") (pin "2") (pinfunction "K_2") (pintype "passive"))
      (node (ref "P2") (pin "2") (pinfunction "2_2") (pintype "passive"))
      (node (ref "P3") (pin "2") (pintype "passive"))
      (node (ref "P3") (pin "3") (pintype "passive"))
      (node (ref "R5") (pin "1") (pinfunction "1_1") (pintype "passive"))
      (node (ref "R8") (pin "1") (pinfunction "1_1") (pintype "passive"))
      (node (ref "RJ1") (pin "10") (pinfunction "10_10") (pintype "passive"))
      (node (ref "RJ1") (pin "14") (pinfunction "14_14") (pintype "passive"))
      (node (ref "RJ1") (pin "20") (pinfunction "20_20") (pintype "passive"))
      (node (ref "RJ1") (pin "26") (pinfunction "26_26") (pintype "passive"))
      (node (ref "RJ1") (pin "4") (pinfunction "4_4") (pintype "passive"))
      (node (ref "RJ2") (pin "14") (pinfunction "14_14") (pintype "passive"))
      (node (ref "RJ2") (pin "2") (pinfunction "2_2") (pintype "passive"))
      (node (ref "RJ2") (pin "22") (pinfunction "22_22") (pintype "passive"))
      (node (ref "RJ2") (pin "28") (pinfunction "28_28") (pintype "passive"))
      (node (ref "RJ2") (pin "8") (pinfunction "8_8") (pintype "passive"))
      (node (ref "RJ3") (pin "2") (pinfunction "2_2") (pintype "passive"))
      (node (ref "RJ4") (pin "2") (pinfunction "2_2") (pintype "passive"))
      (node (ref "RJ5") (pin "2") (pinfunction "2_2") (pintype "passive"))
      (node (ref "RJ6") (pin "2") (pinfunction "2_2") (pintype "passive"))
      (node (ref "S1") (pin "2") (pinfunction "2_2") (pintype "passive"))
      (node (ref "S3") (pin "2") (pinfunction "2_2") (pintype "passive"))
      (node (ref "S4") (pin "2") (pinfunction "2_2") (pintype "passive"))
      (node (ref "U1") (pin "1") (pinfunction "GND_1") (pintype "passive"))
      (node (ref "U2") (pin "10") (pinfunction "VSS_5_10") (pintype "passive"))
      (node (ref "U2") (pin "27") (pinfunction "VSS_4_27") (pintype "passive"))
      (node (ref "U2") (pin "37") (pinfunction "PB2/BOOT1_37") (pintype "passive"))
      (node (ref "U2") (pin "49") (pinfunction "VSS_1_49") (pintype "passive"))
      (node (ref "U2") (pin "74") (pinfunction "VSS_2_74") (pintype "passive"))
      (node (ref "U2") (pin "99") (pinfunction "VSS_3_99") (pintype "passive"))
      (node (ref "U3") (pin "10") (pinfunction "PGND2_10") (pintype "passive"))
      (node (ref "U3") (pin "18") (pinfunction "GND_18") (pintype "passive"))
      (node (ref "U3") (pin "3") (pinfunction "PGND1_3") (pintype "passive"))
      (node (ref "U3") (pin "4") (pinfunction "PGND1_4") (pintype "passive"))
      (node (ref "U3") (pin "9") (pinfunction "PGND2_9") (pintype "passive"))
      (node (ref "U4") (pin "10") (pinfunction "PGND2_10") (pintype "passive"))
      (node (ref "U4") (pin "18") (pinfunction "GND_18") (pintype "passive"))
      (node (ref "U4") (pin "3") (pinfunction "PGND1_3") (pintype "passive"))
      (node (ref "U4") (pin "4") (pinfunction "PGND1_4") (pintype "passive"))
      (node (ref "U4") (pin "9") (pinfunction "PGND2_9") (pintype "passive"))
      (node (ref "U5") (pin "1") (pinfunction "GND_1") (pintype "passive"))
      (node (ref "U6") (pin "1") (pinfunction "A0_1") (pintype "passive"))
      (node (ref "U6") (pin "2") (pinfunction "A1_2") (pintype "passive"))
      (node (ref "U6") (pin "3") (pinfunction "A2_3") (pintype "passive"))
      (node (ref "U6") (pin "4") (pinfunction "GND_4") (pintype "passive"))
      (node (ref "U7") (pin "2") (pinfunction "GND_2") (pintype "passive"))
      (node (ref "U8") (pin "1") (pinfunction "GND_1") (pintype "passive"))
    )
    (net (code "95") (name "Net-(D1-K)") (class "Default")
      (node (ref "D1") (pin "2") (pinfunction "K_2") (pintype "passive"))
      (node (ref "Q1") (pin "3") (pinfunction "C_3") (pintype "passive"))
      (node (ref "R1") (pin "2") (pinfunction "2_2") (pintype "passive"))
    )
    (net (code "96") (name "Net-(D2-A)") (class "Default")
      (node (ref "D2") (pin "1") (pinfunction "A_1") (pintype "passive"))
      (node (ref "J1") (pin "1") (pinfunction "VCC_1") (pintype "passive"))
    )
    (net (code "97") (name "Net-(D3-A)") (class "Default")
      (node (ref "C25") (pin "2") (pinfunction "2_2") (pintype "passive"))
      (node (ref "C26") (pin "1") (pinfunction "1_1") (pintype "passive"))
      (node (ref "D3") (pin "1") (pinfunction "A_1") (pintype "passive"))
      (node (ref "U7") (pin "3") (pinfunction "OUT_3") (pintype "passive"))
    )
    (net (code "98") (name "Net-(F1-Pad2)") (class "Default")
      (node (ref "F1") (pin "2") (pintype "passive"))
      (node (ref "P2") (pin "1") (pinfunction "1_1") (pintype "passive"))
      (node (ref "P3") (pin "1") (pintype "passive"))
    )
    (net (code "99") (name "Net-(LED1-A)") (class "Default")
      (node (ref "LED1") (pin "1") (pinfunction "A_1") (pintype "passive"))
      (node (ref "R11") (pin "1") (pinfunction "1_1") (pintype "passive"))
    )
    (net (code "100") (name "Net-(LED2-A)") (class "Default")
      (node (ref "LED2") (pin "1") (pinfunction "A_1") (pintype "passive"))
      (node (ref "R12") (pin "1") (pinfunction "1_1") (pintype "passive"))
    )
    (net (code "101") (name "Net-(LED3-A)") (class "Default")
      (node (ref "LED3") (pin "1") (pinfunction "A_1") (pintype "passive"))
      (node (ref "R15") (pin "1") (pinfunction "1_1") (pintype "passive"))
    )
    (net (code "102") (name "Net-(LED4-A)") (class "Default")
      (node (ref "LED4") (pin "1") (pinfunction "A_1") (pintype "passive"))
      (node (ref "R17") (pin "1") (pinfunction "1_1") (pintype "passive"))
    )
    (net (code "103") (name "Net-(LED5-A)") (class "Default")
      (node (ref "LED5") (pin "1") (pinfunction "A_1") (pintype "passive"))
      (node (ref "R14") (pin "1") (pinfunction "1_1") (pintype "passive"))
    )
    (net (code "104") (name "Net-(Q1-B)") (class "Default")
      (node (ref "Q1") (pin "1") (pinfunction "B_1") (pintype "passive"))
      (node (ref "R3") (pin "1") (pinfunction "1_1") (pintype "passive"))
    )
    (net (code "105") (name "Net-(Q1-E)") (class "Default")
      (node (ref "Q1") (pin "2") (pinfunction "E_2") (pintype "passive"))
      (node (ref "R4") (pin "2") (pinfunction "2_2") (pintype "passive"))
      (node (ref "U1") (pin "14") (pinfunction "RST#_14") (pintype "passive"))
    )
    (net (code "106") (name "Net-(Q2-B)") (class "Default")
      (node (ref "Q2") (pin "1") (pinfunction "B_1") (pintype "passive"))
      (node (ref "R4") (pin "1") (pinfunction "1_1") (pintype "passive"))
    )
    (net (code "107") (name "Net-(Q2-C)") (class "Default")
      (node (ref "Q2") (pin "3") (pinfunction "C_3") (pintype "passive"))
      (node (ref "R6") (pin "1") (pinfunction "1_1") (pintype "passive"))
    )
    (net (code "108") (name "Net-(U1-DTR#)") (class "Default")
      (node (ref "R3") (pin "2") (pinfunction "2_2") (pintype "passive"))
      (node (ref "U1") (pin "13") (pinfunction "DTR#_13") (pintype "passive"))
    )
    (net (code "109") (name "Net-(U1-V3)") (class "Default")
      (node (ref "C3") (pin "2") (pinfunction "2_2") (pintype "passive"))
      (node (ref "U1") (pin "4") (pinfunction "V3_4") (pintype "passive"))
    )
    (net (code "110") (name "USB_5V") (class "Default")
      (node (ref "D2") (pin "2") (pinfunction "K_2") (pintype "passive"))
      (node (ref "D3") (pin "2") (pinfunction "K_2") (pintype "passive"))
      (node (ref "S2") (pin "1") (pinfunction "1_1") (pintype "passive"))
    )
    (net (code "111") (name "VCC3.3") (class "Default")
      (node (ref "C13") (pin "2") (pinfunction "2_2") (pintype "passive"))
      (node (ref "C14") (pin "2") (pinfunction "2_2") (pintype "passive"))
      (node (ref "C15") (pin "2") (pinfunction "2_2") (pintype "passive"))
      (node (ref "C16") (pin "2") (pinfunction "2_2") (pintype "passive"))
      (node (ref "C17") (pin "2") (pinfunction "2_2") (pintype "passive"))
      (node (ref "C19") (pin "2") (pinfunction "2_2") (pintype "passive"))
      (node (ref "C21") (pin "2") (pinfunction "2_2") (pintype "passive"))
      (node (ref "C22") (pin "2") (pinfunction "2_2") (pintype "passive"))
      (node (ref "C27") (pin "2") (pinfunction "2_2") (pintype "passive"))
      (node (ref "Q2") (pin "2") (pinfunction "E_2") (pintype "passive"))
      (node (ref "R1") (pin "1") (pinfunction "1_1") (pintype "passive"))
      (node (ref "R10") (pin "1") (pinfunction "1_1") (pintype "passive"))
      (node (ref "R13") (pin "1") (pinfunction "1_1") (pintype "passive"))
      (node (ref "R16") (pin "1") (pinfunction "1_1") (pintype "passive"))
      (node (ref "R2") (pin "2") (pinfunction "2_2") (pintype "passive"))
      (node (ref "R9") (pin "1") (pinfunction "1_1") (pintype "passive"))
      (node (ref "U2") (pin "100") (pinfunction "VDD_3_100") (pintype "passive"))
      (node (ref "U2") (pin "11") (pinfunction "VDD_5_11") (pintype "passive"))
      (node (ref "U2") (pin "21") (pinfunction "VREF+_21") (pintype "passive"))
      (node (ref "U2") (pin "22") (pinfunction "VDDA_22") (pintype "passive"))
      (node (ref "U2") (pin "28") (pinfunction "VDD_4_28") (pintype "passive"))
      (node (ref "U2") (pin "50") (pinfunction "VDD_1_50") (pintype "passive"))
      (node (ref "U2") (pin "6") (pinfunction "VBAT_6") (pintype "passive"))
      (node (ref "U2") (pin "75") (pinfunction "VDD_2_75") (pintype "passive"))
      (node (ref "U3") (pin "20") (pinfunction "VCC_20") (pintype "passive"))
      (node (ref "U4") (pin "20") (pinfunction "VCC_20") (pintype "passive"))
      (node (ref "U5") (pin "2") (pinfunction "VCC_2") (pintype "passive"))
      (node (ref "U6") (pin "8") (pinfunction "VCC_8") (pintype "passive"))
      (node (ref "U8") (pin "2") (pinfunction "OUT_2") (pintype "passive"))
    )
    (net (code "112") (name "VCC5") (class "Default")
      (node (ref "C1") (pin "1") (pinfunction "1_1") (pintype "passive"))
      (node (ref "C2") (pin "1") (pinfunction "1_1") (pintype "passive"))
      (node (ref "C28") (pin "2") (pinfunction "2_2") (pintype "passive"))
      (node (ref "P1") (pin "1") (pinfunction "1_1") (pintype "passive"))
      (node (ref "R14") (pin "2") (pinfunction "2_2") (pintype "passive"))
      (node (ref "RJ1") (pin "11") (pinfunction "11_11") (pintype "passive"))
      (node (ref "RJ1") (pin "15") (pinfunction "15_15") (pintype "passive"))
      (node (ref "RJ1") (pin "21") (pinfunction "21_21") (pintype "passive"))
      (node (ref "RJ1") (pin "27") (pinfunction "27_27") (pintype "passive"))
      (node (ref "RJ1") (pin "5") (pinfunction "5_5") (pintype "passive"))
      (node (ref "RJ2") (pin "15") (pinfunction "15_15") (pintype "passive"))
      (node (ref "RJ2") (pin "23") (pinfunction "23_23") (pintype "passive"))
      (node (ref "RJ2") (pin "29") (pinfunction "29_29") (pintype "passive"))
      (node (ref "RJ2") (pin "3") (pinfunction "3_3") (pintype "passive"))
      (node (ref "RJ2") (pin "9") (pinfunction "9_9") (pintype "passive"))
      (node (ref "RJ3") (pin "3") (pinfunction "3_3") (pintype "passive"))
      (node (ref "RJ4") (pin "3") (pinfunction "3_3") (pintype "passive"))
      (node (ref "RJ5") (pin "3") (pinfunction "3_3") (pintype "passive"))
      (node (ref "RJ6") (pin "3") (pinfunction "3_3") (pintype "passive"))
      (node (ref "S2") (pin "2") (pinfunction "2_2") (pintype "passive"))
      (node (ref "U1") (pin "16") (pinfunction "VCC_16") (pintype "passive"))
      (node (ref "U8") (pin "3") (pinfunction "IN_3") (pintype "passive"))
    )
    (net (code "113") (name "VS") (class "Default")
      (node (ref "C23") (pin "1") (pinfunction "1_1") (pintype "passive"))
      (node (ref "C24") (pin "2") (pinfunction "2_2") (pintype "passive"))
      (node (ref "F1") (pin "1") (pintype "passive"))
      (node (ref "P1") (pin "3") (pinfunction "3_3") (pintype "passive"))
      (node (ref "U7") (pin "1") (pinfunction "IN_1") (pintype "passive"))
    )
    (net (code "114") (name "unconnected-(M1-Pad0)") (class "Default")
      (node (ref "M1") (pin "0") (pinfunction "0_0") (pintype "passive"))
    )
    (net (code "115") (name "unconnected-(M2-Pad0)") (class "Default")
      (node (ref "M2") (pin "0") (pinfunction "0_0") (pintype "passive"))
    )
    (net (code "116") (name "unconnected-(M3-Pad0)") (class "Default")
      (node (ref "M3") (pin "0") (pinfunction "0_0") (pintype "passive"))
    )
    (net (code "117") (name "unconnected-(M4-Pad0)") (class "Default")
      (node (ref "M4") (pin "0") (pinfunction "0_0") (pintype "passive"))
    )
    (net (code "118") (name "unconnected-(RJ1-Pad6)") (class "Default")
      (node (ref "RJ1") (pin "6") (pinfunction "6_6") (pintype "passive+no_connect"))
    )
    (net (code "119") (name "unconnected-(RJ1-Pad12)") (class "Default")
      (node (ref "RJ1") (pin "12") (pinfunction "12_12") (pintype "passive+no_connect"))
    )
    (net (code "120") (name "unconnected-(RJ2-Pad24)") (class "Default")
      (node (ref "RJ2") (pin "24") (pinfunction "24_24") (pintype "passive+no_connect"))
    )
    (net (code "121") (name "unconnected-(RJ2-Pad30)") (class "Default")
      (node (ref "RJ2") (pin "30") (pinfunction "30_30") (pintype "passive+no_connect"))
    )
    (net (code "122") (name "unconnected-(U1-CTS#-Pad9)") (class "Default")
      (node (ref "U1") (pin "9") (pinfunction "CTS#_9") (pintype "passive+no_connect"))
    )
    (net (code "123") (name "unconnected-(U1-DCD#-Pad12)") (class "Default")
      (node (ref "U1") (pin "12") (pinfunction "DCD#_12") (pintype "passive+no_connect"))
    )
    (net (code "124") (name "unconnected-(U1-DSR#-Pad10)") (class "Default")
      (node (ref "U1") (pin "10") (pinfunction "DSR#_10") (pintype "passive+no_connect"))
    )
    (net (code "125") (name "unconnected-(U1-R232-Pad15)") (class "Default")
      (node (ref "U1") (pin "15") (pinfunction "R232_15") (pintype "passive+no_connect"))
    )
    (net (code "126") (name "unconnected-(U1-RI#-Pad11)") (class "Default")
      (node (ref "U1") (pin "11") (pinfunction "RI#_11") (pintype "passive+no_connect"))
    )
    (net (code "127") (name "unconnected-(U2-NC-Pad73)") (class "Default")
      (node (ref "U2") (pin "73") (pinfunction "NC_73") (pintype "passive+no_connect"))
    )
    (net (code "128") (name "unconnected-(U2-PC13{slash}TAMPER-RTC-Pad7)") (class "Default")
      (node (ref "U2") (pin "7") (pinfunction "PC13/TAMPER-RTC_7") (pintype "passive+no_connect"))
    )
    (net (code "129") (name "unconnected-(U2-PE7{slash}FSMC_D4-Pad38)") (class "Default")
      (node (ref "U2") (pin "38") (pinfunction "PE7/FSMC_D4_38") (pintype "passive+no_connect"))
    )
    (net (code "130") (name "unconnected-(U2-PE8{slash}FSMC_D5-Pad39)") (class "Default")
      (node (ref "U2") (pin "39") (pinfunction "PE8/FSMC_D5_39") (pintype "passive+no_connect"))
    )
    (net (code "131") (name "unconnected-(U2-PE9{slash}FSMC_D6-Pad40)") (class "Default")
      (node (ref "U2") (pin "40") (pinfunction "PE9/FSMC_D6_40") (pintype "passive+no_connect"))
    )
    (net (code "132") (name "unconnected-(U8-OUT-Pad4)") (class "Default")
      (node (ref "U8") (pin "4") (pinfunction "OUT_4") (pintype "passive+no_connect"))
    )
  )
)
